# main.net
KiCad netlist of a schematic drawn in EAGLE
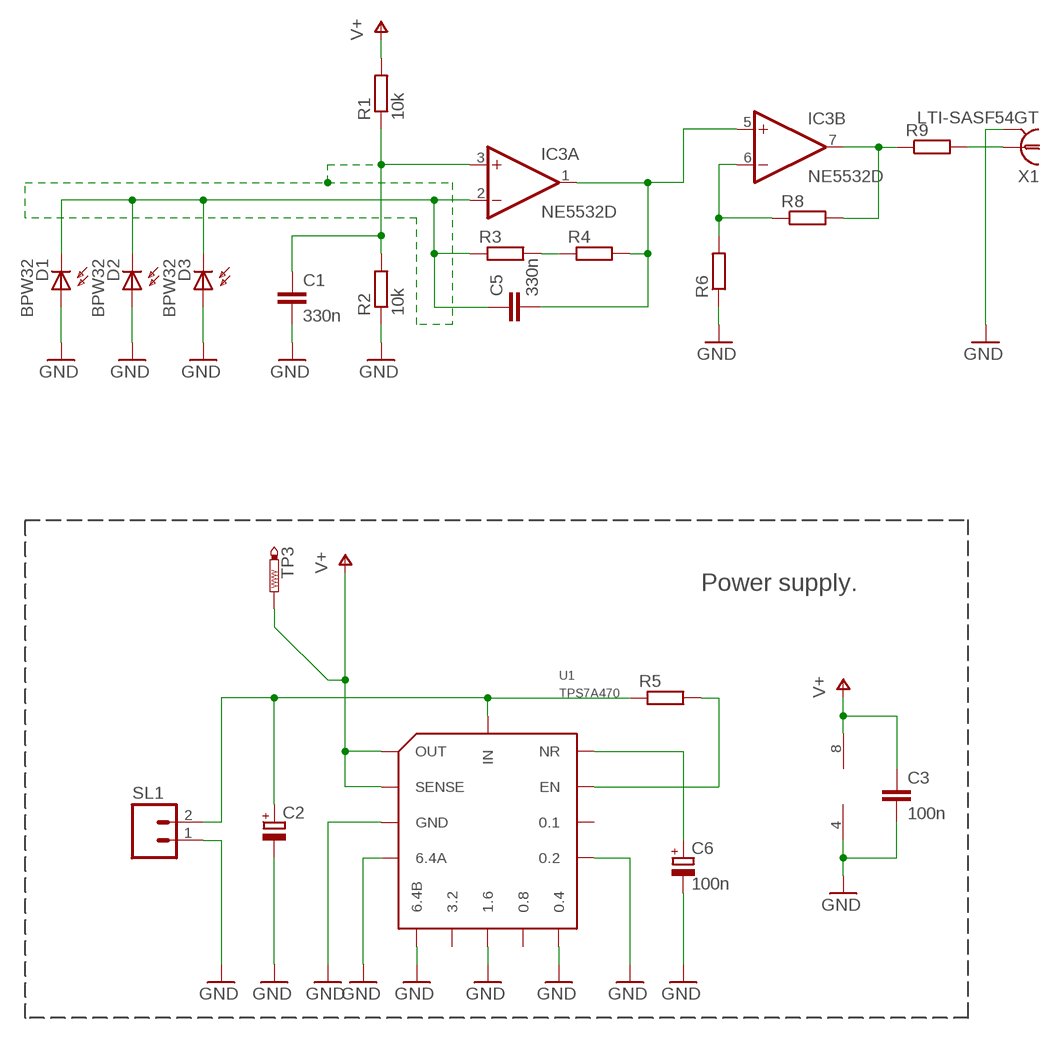
[diagram p0: schematic, sheet 1]

(export (version "E")
  (design (tool "Eeschema 10.0.6"))
  (components
    (comp (ref "C1")
      (value "330n")
      (footprint "eagle-import:C0805")
      (libsource (lib "eagle-import") (part "C-EUC0805"))
    )
    (comp (ref "C2")
      (value "CPOL-EUT/3528-12R")
      (footprint "eagle-import:T_3528-12R")
      (libsource (lib "eagle-import") (part "CPOL-EUT/3528-12R"))
    )
    (comp (ref "C3")
      (value "100n")
      (footprint "eagle-import:C0805")
      (libsource (lib "eagle-import") (part "C-EUC0805"))
    )
    (comp (ref "C5")
      (value "330n")
      (footprint "eagle-import:C0805")
      (libsource (lib "eagle-import") (part "C-EUC0805"))
    )
    (comp (ref "C6")
      (value "100n")
      (footprint "eagle-import:A_3216-18W")
      (libsource (lib "eagle-import") (part "CPOL-EUA/3216-18W"))
    )
    (comp (ref "D1")
      (value "BPW32")
      (footprint "eagle-import:BPW32")
      (libsource (lib "eagle-import") (part "BPW32"))
    )
    (comp (ref "D2")
      (value "BPW32")
      (footprint "eagle-import:BPW32")
      (libsource (lib "eagle-import") (part "BPW32"))
    )
    (comp (ref "D3")
      (value "BPW32")
      (footprint "eagle-import:BPW32")
      (libsource (lib "eagle-import") (part "BPW32"))
    )
    (comp (ref "IC3")
      (value "NE5532D")
      (footprint "eagle-import:SO08")
      (libsource (lib "eagle-import") (part "NE5532D"))
    )
    (comp (ref "R1")
      (value "10k")
      (footprint "eagle-import:R0805")
      (libsource (lib "eagle-import") (part "R-EU_R0805"))
    )
    (comp (ref "R2")
      (value "10k")
      (footprint "eagle-import:R0805")
      (libsource (lib "eagle-import") (part "R-EU_R0805"))
    )
    (comp (ref "R3")
      (value "R-EU_MELF0204W")
      (footprint "eagle-import:MINI_MELF-0204W")
      (libsource (lib "eagle-import") (part "resistor_R-EU_MELF0204W"))
    )
    (comp (ref "R4")
      (value "R-EU_MELF0204W")
      (footprint "eagle-import:MINI_MELF-0204W")
      (libsource (lib "eagle-import") (part "resistor_R-EU_MELF0204W"))
    )
    (comp (ref "R5")
      (value "R-EU_M1206")
      (footprint "eagle-import:M1206")
      (libsource (lib "eagle-import") (part "resistor_R-EU_M1206"))
    )
    (comp (ref "R6")
      (value "R-EU_0204/2V")
      (footprint "eagle-import:0204V")
      (libsource (lib "eagle-import") (part "resistor_R-EU_0204/2V"))
    )
    (comp (ref "R8")
      (value "R-EU_M0805")
      (footprint "eagle-import:M0805")
      (libsource (lib "eagle-import") (part "resistor_R-EU_M0805"))
    )
    (comp (ref "R9")
      (value "R-EU_0204/2V")
      (footprint "eagle-import:0204V")
      (libsource (lib "eagle-import") (part "resistor_R-EU_0204/2V"))
    )
    (comp (ref "SL1")
      (value "M02")
      (footprint "eagle-import:02P")
      (libsource (lib "eagle-import") (part "M02"))
    )
    (comp (ref "TP3")
      (value "PTR1TP12R")
      (footprint "eagle-import:TP12R")
      (libsource (lib "eagle-import") (part "PTR1TP12R"))
    )
    (comp (ref "U1")
      (value "TPS7A470")
      (footprint "eagle-import:S-PVQFN-N20")
      (libsource (lib "eagle-import") (part "TPS7A470"))
    )
    (comp (ref "X1")
      (value "LTI-SASF54GT")
      (footprint "eagle-import:LTI-SASF54GT")
      (libsource (lib "eagle-import") (part "LTI-SASF54GT"))
    )
  )
  (nets
    (net (code "1") (name "GND") (class "Default")
      (node (ref "C1") (pin "2") (pinfunction "2_2") (pintype "passive"))
      (node (ref "C2") (pin "-") (pinfunction "-_-") (pintype "passive"))
      (node (ref "C3") (pin "2") (pinfunction "2_2") (pintype "passive"))
      (node (ref "C6") (pin "-") (pinfunction "-_-") (pintype "passive"))
      (node (ref "D1") (pin "A") (pinfunction "A_A") (pintype "passive"))
      (node (ref "D2") (pin "A") (pinfunction "A_A") (pintype "passive"))
      (node (ref "D3") (pin "A") (pinfunction "A_A") (pintype "passive"))
      (node (ref "IC3") (pin "4") (pinfunction "V-_4") (pintype "power_in"))
      (node (ref "R2") (pin "1") (pinfunction "1_1") (pintype "passive"))
      (node (ref "R6") (pin "1") (pinfunction "1_1") (pintype "passive"))
      (node (ref "SL1") (pin "1") (pinfunction "1_1") (pintype "passive"))
      (node (ref "U1") (pin "10") (pinfunction "0.4_10") (pintype "bidirectional"))
      (node (ref "U1") (pin "11") (pinfunction "0.2_11") (pintype "bidirectional"))
      (node (ref "U1") (pin "17") (pinfunction "GND_17") (pintype "bidirectional"))
      (node (ref "U1") (pin "18") (pinfunction "GND_18") (pintype "bidirectional"))
      (node (ref "U1") (pin "19") (pinfunction "GND_19") (pintype "bidirectional"))
      (node (ref "U1") (pin "2") (pinfunction "GND_2") (pintype "bidirectional"))
      (node (ref "U1") (pin "4") (pinfunction "6.4A_4") (pintype "bidirectional"))
      (node (ref "U1") (pin "5") (pinfunction "6.4B_5") (pintype "bidirectional"))
      (node (ref "U1") (pin "7") (pinfunction "GND_7") (pintype "bidirectional"))
      (node (ref "U1") (pin "8") (pinfunction "1.6_8") (pintype "bidirectional"))
      (node (ref "U1") (pin "EXP") (pinfunction "GND_EXP") (pintype "bidirectional"))
      (node (ref "X1") (pin "2") (pinfunction "2_2") (pintype "passive"))
      (node (ref "X1") (pin "3") (pinfunction "2_3") (pintype "passive"))
      (node (ref "X1") (pin "4") (pinfunction "2_4") (pintype "passive"))
      (node (ref "X1") (pin "5") (pinfunction "2_5") (pintype "passive"))
    )
    (net (code "2") (name "Net-(C2-Pad+)") (class "Default")
      (node (ref "C2") (pin "+") (pinfunction "+_+") (pintype "passive"))
      (node (ref "R5") (pin "1") (pinfunction "1_1") (pintype "passive"))
      (node (ref "SL1") (pin "2") (pinfunction "2_2") (pintype "passive"))
      (node (ref "U1") (pin "15") (pinfunction "IN_15") (pintype "bidirectional"))
      (node (ref "U1") (pin "16") (pinfunction "IN_16") (pintype "bidirectional"))
    )
    (net (code "3") (name "Net-(D1-C)") (class "Default")
      (node (ref "C5") (pin "1") (pinfunction "1_1") (pintype "passive"))
      (node (ref "D1") (pin "K") (pinfunction "C_K") (pintype "passive"))
      (node (ref "D2") (pin "K") (pinfunction "C_K") (pintype "passive"))
      (node (ref "D3") (pin "K") (pinfunction "C_K") (pintype "passive"))
      (node (ref "IC3") (pin "2") (pinfunction "-IN_2") (pintype "input"))
      (node (ref "R3") (pin "1") (pinfunction "1_1") (pintype "passive"))
    )
    (net (code "4") (name "Net-(IC3A-+IN)") (class "Default")
      (node (ref "C1") (pin "1") (pinfunction "1_1") (pintype "passive"))
      (node (ref "IC3") (pin "3") (pinfunction "+IN_3") (pintype "input"))
      (node (ref "R1") (pin "1") (pinfunction "1_1") (pintype "passive"))
      (node (ref "R2") (pin "2") (pinfunction "2_2") (pintype "passive"))
    )
    (net (code "5") (name "Net-(IC3A-OUT)") (class "Default")
      (node (ref "C5") (pin "2") (pinfunction "2_2") (pintype "passive"))
      (node (ref "IC3") (pin "1") (pinfunction "OUT_1") (pintype "output"))
      (node (ref "IC3") (pin "5") (pinfunction "+IN_5") (pintype "input"))
      (node (ref "R4") (pin "2") (pinfunction "2_2") (pintype "passive"))
    )
    (net (code "6") (name "Net-(IC3B--IN)") (class "Default")
      (node (ref "IC3") (pin "6") (pinfunction "-IN_6") (pintype "input"))
      (node (ref "R6") (pin "2") (pinfunction "2_2") (pintype "passive"))
      (node (ref "R8") (pin "1") (pinfunction "1_1") (pintype "passive"))
    )
    (net (code "7") (name "Net-(IC3B-OUT)") (class "Default")
      (node (ref "IC3") (pin "7") (pinfunction "OUT_7") (pintype "output"))
      (node (ref "R8") (pin "2") (pinfunction "2_2") (pintype "passive"))
      (node (ref "R9") (pin "1") (pinfunction "1_1") (pintype "passive"))
    )
    (net (code "8") (name "Net-(R3-Pad2)") (class "Default")
      (node (ref "R3") (pin "2") (pinfunction "2_2") (pintype "passive"))
      (node (ref "R4") (pin "1") (pinfunction "1_1") (pintype "passive"))
    )
    (net (code "9") (name "Net-(R9-Pad2)") (class "Default")
      (node (ref "R9") (pin "2") (pinfunction "2_2") (pintype "passive"))
      (node (ref "X1") (pin "1") (pinfunction "1_1") (pintype "passive"))
    )
    (net (code "10") (name "Net-(U1-EN)") (class "Default")
      (node (ref "R5") (pin "2") (pinfunction "2_2") (pintype "passive"))
      (node (ref "U1") (pin "13") (pinfunction "EN_13") (pintype "bidirectional"))
    )
    (net (code "11") (name "Net-(U1-NR)") (class "Default")
      (node (ref "C6") (pin "+") (pinfunction "+_+") (pintype "passive"))
      (node (ref "U1") (pin "14") (pinfunction "NR_14") (pintype "bidirectional"))
    )
    (net (code "12") (name "V+") (class "Default")
      (node (ref "C3") (pin "1") (pinfunction "1_1") (pintype "passive"))
      (node (ref "IC3") (pin "8") (pinfunction "V+_8") (pintype "power_in"))
      (node (ref "R1") (pin "2") (pinfunction "2_2") (pintype "passive"))
      (node (ref "TP3") (pin "TP") (pinfunction "TP_TP") (pintype "input"))
      (node (ref "U1") (pin "1") (pinfunction "OUT_1") (pintype "bidirectional"))
      (node (ref "U1") (pin "20") (pinfunction "OUT_20") (pintype "bidirectional"))
      (node (ref "U1") (pin "3") (pinfunction "SENSE_3") (pintype "bidirectional"))
    )
    (net (code "13") (name "unconnected-(U1-0.1-Pad12)") (class "Default")
      (node (ref "U1") (pin "12") (pinfunction "0.1_12") (pintype "bidirectional"))
    )
    (net (code "14") (name "unconnected-(U1-0.8-Pad9)") (class "Default")
      (node (ref "U1") (pin "9") (pinfunction "0.8_9") (pintype "bidirectional"))
    )
    (net (code "15") (name "unconnected-(U1-3.2-Pad6)") (class "Default")
      (node (ref "U1") (pin "6") (pinfunction "3.2_6") (pintype "bidirectional"))
    )
  )
)
